# PCB_CHECKV3_2-20201218.net
KiCad netlist of a schematic drawn in Altium Designer
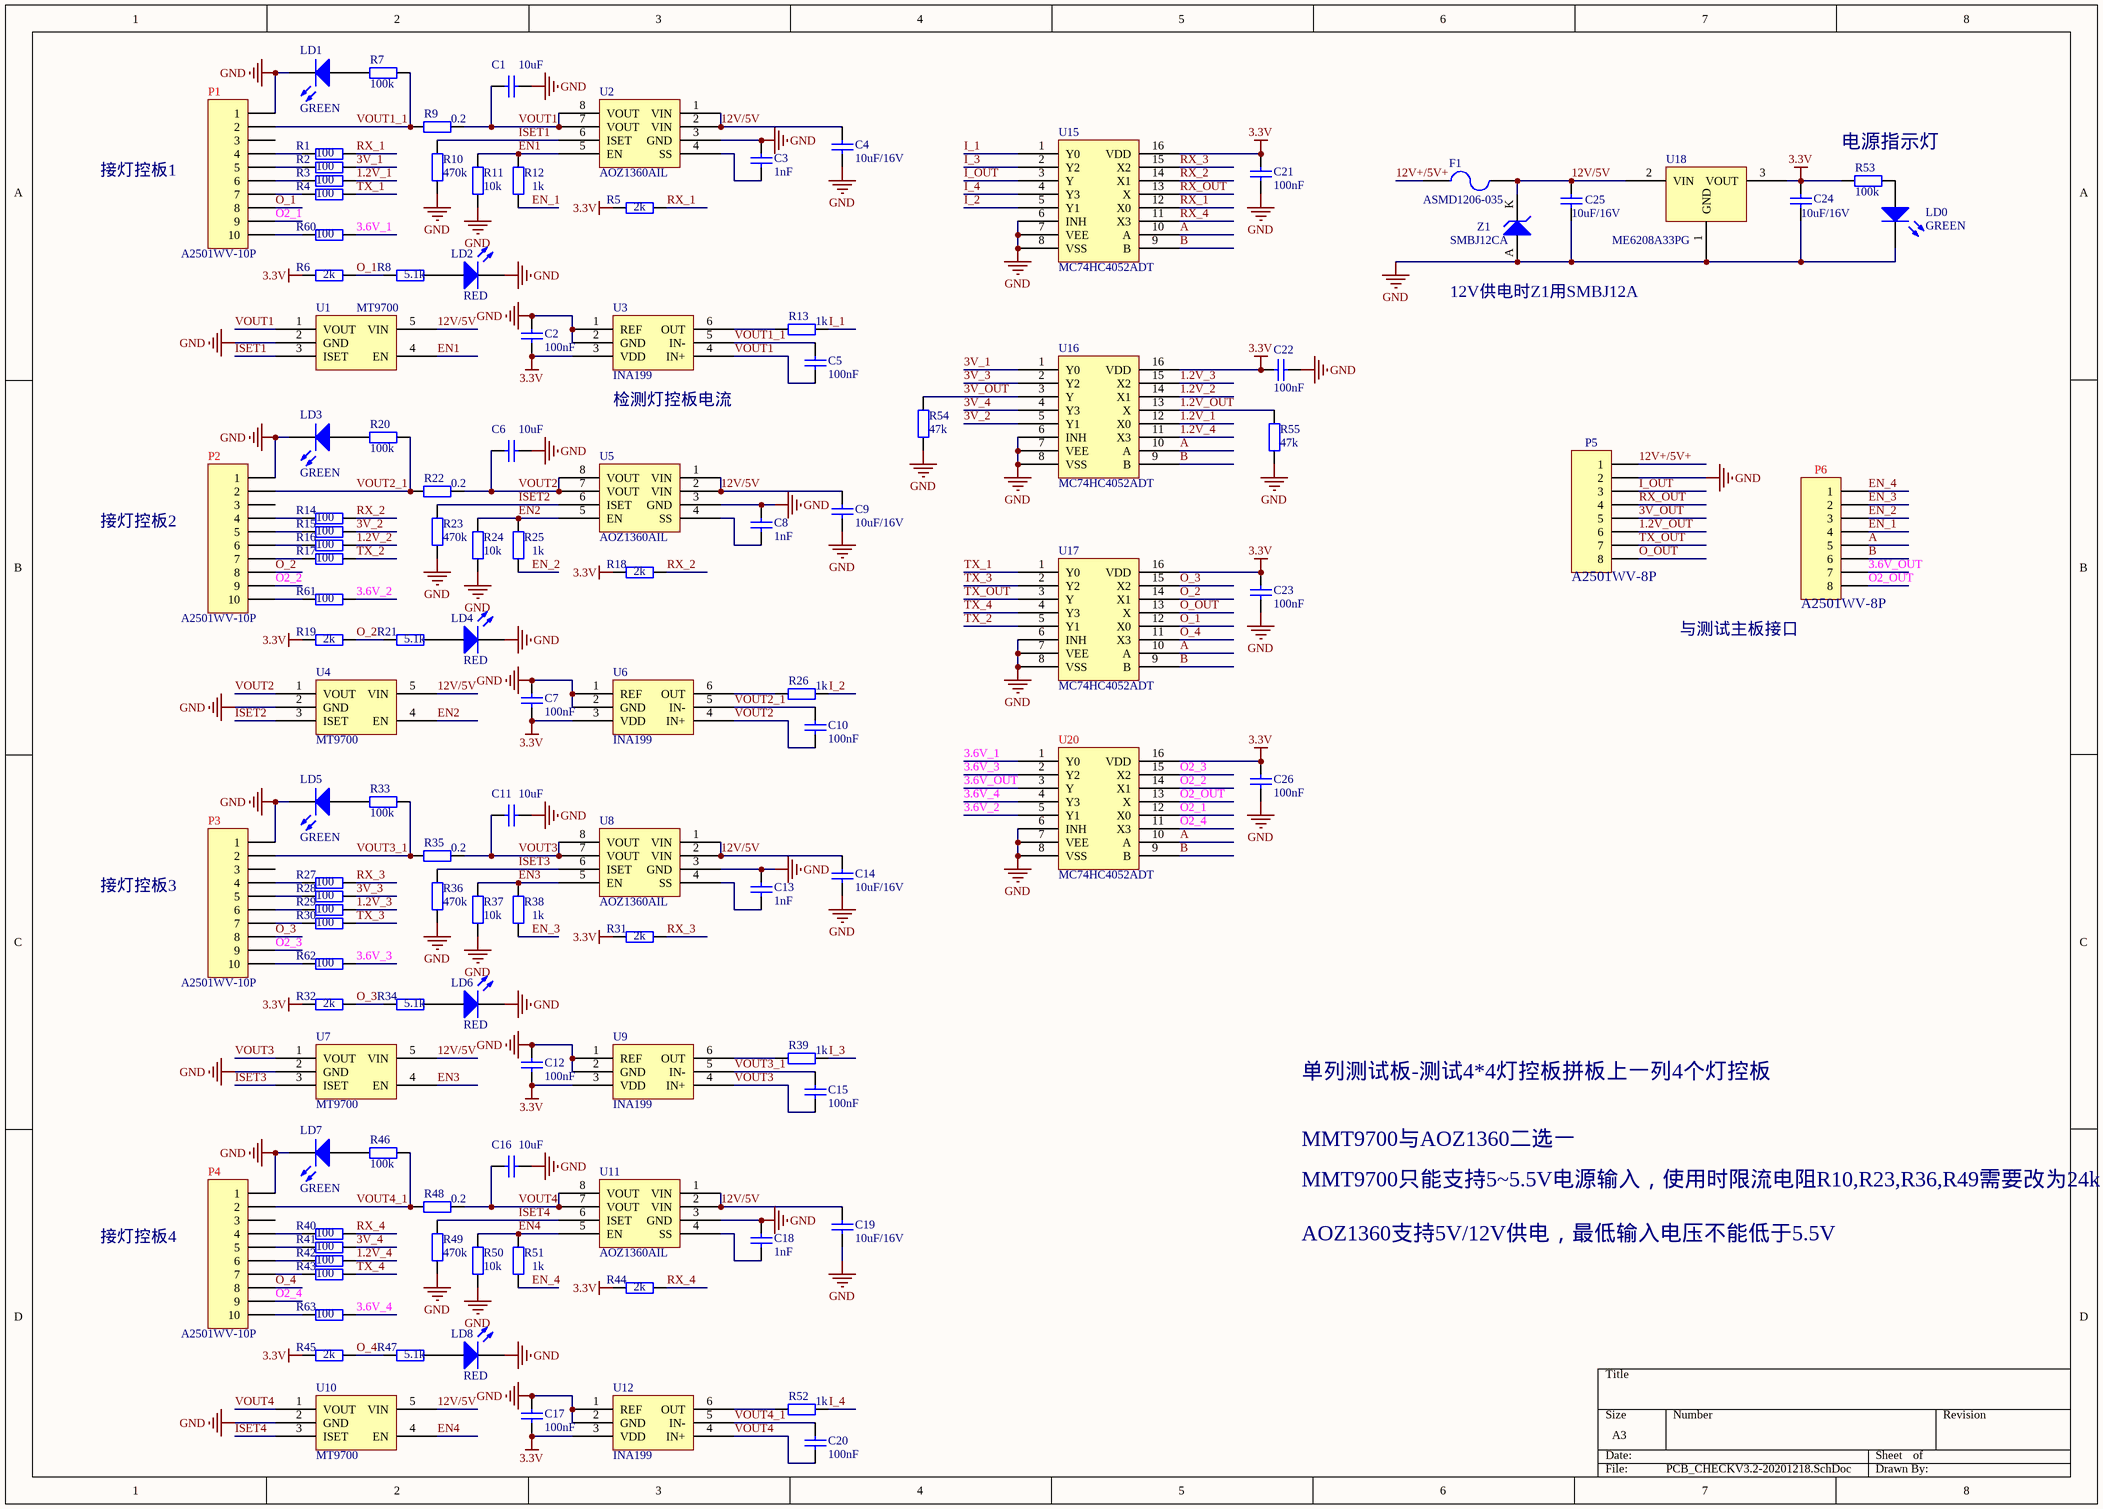
[diagram p0: PCB_CHECKV3.2-20201218.SchDoc]

(export (version "E")
  (design (tool "Eeschema 10.0.6"))
  (components
    (comp (ref "C1")
      (value "10uF")
      (footprint "C0603")
      (description "Capacitor")
      (libsource (lib "Miscellaneous Devices") (part "Cap"))
    )
    (comp (ref "C2")
      (value "100nF")
      (footprint "C0603")
      (description "Capacitor")
      (libsource (lib "Miscellaneous Devices") (part "Cap"))
    )
    (comp (ref "C3")
      (value "1nF")
      (footprint "C0603")
      (description "Capacitor")
      (libsource (lib "Miscellaneous Devices") (part "Cap"))
    )
    (comp (ref "C4")
      (value "10uF/16V")
      (footprint "C0603")
      (description "Capacitor")
      (libsource (lib "Miscellaneous Devices") (part "Cap"))
    )
    (comp (ref "C5")
      (value "100nF")
      (footprint "C0603")
      (description "Capacitor")
      (libsource (lib "Miscellaneous Devices") (part "Cap"))
    )
    (comp (ref "C6")
      (value "10uF")
      (footprint "C0603")
      (description "Capacitor")
      (libsource (lib "Miscellaneous Devices") (part "Cap"))
    )
    (comp (ref "C7")
      (value "100nF")
      (footprint "C0603")
      (description "Capacitor")
      (libsource (lib "Miscellaneous Devices") (part "Cap"))
    )
    (comp (ref "C8")
      (value "1nF")
      (footprint "C0603")
      (description "Capacitor")
      (libsource (lib "Miscellaneous Devices") (part "Cap"))
    )
    (comp (ref "C9")
      (value "10uF/16V")
      (footprint "C0603")
      (description "Capacitor")
      (libsource (lib "Miscellaneous Devices") (part "Cap"))
    )
    (comp (ref "C10")
      (value "100nF")
      (footprint "C0603")
      (description "Capacitor")
      (libsource (lib "Miscellaneous Devices") (part "Cap"))
    )
    (comp (ref "C11")
      (value "10uF")
      (footprint "C0603")
      (description "Capacitor")
      (libsource (lib "Miscellaneous Devices") (part "Cap"))
    )
    (comp (ref "C12")
      (value "100nF")
      (footprint "C0603")
      (description "Capacitor")
      (libsource (lib "Miscellaneous Devices") (part "Cap"))
    )
    (comp (ref "C13")
      (value "1nF")
      (footprint "C0603")
      (description "Capacitor")
      (libsource (lib "Miscellaneous Devices") (part "Cap"))
    )
    (comp (ref "C14")
      (value "10uF/16V")
      (footprint "C0603")
      (description "Capacitor")
      (libsource (lib "Miscellaneous Devices") (part "Cap"))
    )
    (comp (ref "C15")
      (value "100nF")
      (footprint "C0603")
      (description "Capacitor")
      (libsource (lib "Miscellaneous Devices") (part "Cap"))
    )
    (comp (ref "C16")
      (value "10uF")
      (footprint "C0603")
      (description "Capacitor")
      (libsource (lib "Miscellaneous Devices") (part "Cap"))
    )
    (comp (ref "C17")
      (value "100nF")
      (footprint "C0603")
      (description "Capacitor")
      (libsource (lib "Miscellaneous Devices") (part "Cap"))
    )
    (comp (ref "C18")
      (value "1nF")
      (footprint "C0603")
      (description "Capacitor")
      (libsource (lib "Miscellaneous Devices") (part "Cap"))
    )
    (comp (ref "C19")
      (value "10uF/16V")
      (footprint "C0603")
      (description "Capacitor")
      (libsource (lib "Miscellaneous Devices") (part "Cap"))
    )
    (comp (ref "C20")
      (value "100nF")
      (footprint "C0603")
      (description "Capacitor")
      (libsource (lib "Miscellaneous Devices") (part "Cap"))
    )
    (comp (ref "C21")
      (value "100nF")
      (footprint "C0603")
      (description "Capacitor")
      (libsource (lib "Miscellaneous Devices") (part "Cap"))
    )
    (comp (ref "C22")
      (value "100nF")
      (footprint "C0603")
      (description "Capacitor")
      (libsource (lib "Miscellaneous Devices") (part "Cap"))
    )
    (comp (ref "C23")
      (value "100nF")
      (footprint "C0603")
      (description "Capacitor")
      (libsource (lib "Miscellaneous Devices") (part "Cap"))
    )
    (comp (ref "C24")
      (value "10uF/16V")
      (footprint "C0603")
      (description "Capacitor")
      (libsource (lib "Miscellaneous Devices") (part "Cap"))
    )
    (comp (ref "C25")
      (value "10uF/16V")
      (footprint "C0603")
      (description "Capacitor")
      (libsource (lib "Miscellaneous Devices") (part "Cap"))
    )
    (comp (ref "C26")
      (value "100nF")
      (footprint "C0603")
      (description "Capacitor")
      (libsource (lib "Miscellaneous Devices") (part "Cap"))
    )
    (comp (ref "F1")
      (value "ASMD1206-035")
      (footprint "R1206")
      (description "Fuse")
      (libsource (lib "Miscellaneous Devices") (part "Fuse 2"))
    )
    (comp (ref "LD0")
      (value "GREEN")
      (footprint "LED-0603")
      (description "LED灯")
      (libsource (lib "*") (part "LED0"))
    )
    (comp (ref "LD1")
      (value "GREEN")
      (footprint "LED-0603")
      (description "LED灯")
      (libsource (lib "*") (part "LED0"))
    )
    (comp (ref "LD2")
      (value "RED")
      (footprint "LED-0603")
      (description "LED灯")
      (libsource (lib "*") (part "LED0"))
    )
    (comp (ref "LD3")
      (value "GREEN")
      (footprint "LED-0603")
      (description "LED灯")
      (libsource (lib "*") (part "LED0"))
    )
    (comp (ref "LD4")
      (value "RED")
      (footprint "LED-0603")
      (description "LED灯")
      (libsource (lib "*") (part "LED0"))
    )
    (comp (ref "LD5")
      (value "GREEN")
      (footprint "LED-0603")
      (description "LED灯")
      (libsource (lib "*") (part "LED0"))
    )
    (comp (ref "LD6")
      (value "RED")
      (footprint "LED-0603")
      (description "LED灯")
      (libsource (lib "*") (part "LED0"))
    )
    (comp (ref "LD7")
      (value "GREEN")
      (footprint "LED-0603")
      (description "LED灯")
      (libsource (lib "*") (part "LED0"))
    )
    (comp (ref "LD8")
      (value "RED")
      (footprint "LED-0603")
      (description "LED灯")
      (libsource (lib "*") (part "LED0"))
    )
    (comp (ref "P1")
      (value "A2501WV-10P")
      (footprint "XH2.5-8P")
      (description "Header, 8-Pin")
      (libsource (lib "PCB_CHECKV3.2-20201218") (part "Header 10"))
    )
    (comp (ref "P2")
      (value "A2501WV-10P")
      (footprint "XH2.5-8P")
      (description "Header, 8-Pin")
      (libsource (lib "PCB_CHECKV3.2-20201218") (part "Header 10"))
    )
    (comp (ref "P3")
      (value "A2501WV-10P")
      (footprint "XH2.5-8P")
      (description "Header, 8-Pin")
      (libsource (lib "PCB_CHECKV3.2-20201218") (part "Header 10"))
    )
    (comp (ref "P4")
      (value "A2501WV-10P")
      (footprint "XH2.5-8P")
      (description "Header, 8-Pin")
      (libsource (lib "PCB_CHECKV3.2-20201218") (part "Header 10"))
    )
    (comp (ref "P5")
      (value "A2501WV-8P")
      (footprint "XH2.5-8P")
      (description "Header, 8-Pin")
      (libsource (lib "Miscellaneous Connectors") (part "Header 8"))
    )
    (comp (ref "P6")
      (value "A2501WV-8P")
      (footprint "XH2.5-8P")
      (description "Header, 8-Pin")
      (libsource (lib "Miscellaneous Connectors") (part "Header 8"))
    )
    (comp (ref "R1")
      (value "100")
      (footprint "R0603")
      (description "Resistor")
      (libsource (lib "") (part "Res2_1"))
    )
    (comp (ref "R2")
      (value "100")
      (footprint "R0603")
      (description "Resistor")
      (libsource (lib "") (part "Res2_1"))
    )
    (comp (ref "R3")
      (value "100")
      (footprint "R0603")
      (description "Resistor")
      (libsource (lib "") (part "Res2_1"))
    )
    (comp (ref "R4")
      (value "100")
      (footprint "R0603")
      (description "Resistor")
      (libsource (lib "") (part "Res2_1"))
    )
    (comp (ref "R5")
      (value "2k")
      (footprint "R0603")
      (description "Resistor")
      (libsource (lib "") (part "Res2_1"))
    )
    (comp (ref "R6")
      (value "2k")
      (footprint "R0603")
      (description "Resistor")
      (libsource (lib "") (part "Res2_1"))
    )
    (comp (ref "R7")
      (value "100k")
      (footprint "R0603")
      (description "Resistor")
      (libsource (lib "") (part "Res2_2"))
    )
    (comp (ref "R8")
      (value "5.1k")
      (footprint "R0603")
      (description "Resistor")
      (libsource (lib "") (part "Res2_1"))
    )
    (comp (ref "R9")
      (value "0.2")
      (footprint "R0603")
      (description "Resistor")
      (libsource (lib "") (part "Res2_1"))
    )
    (comp (ref "R10")
      (value "470k")
      (footprint "R0603")
      (description "Resistor")
      (libsource (lib "Miscellaneous Devices") (part "Res2"))
    )
    (comp (ref "R11")
      (value "10k")
      (footprint "R0603")
      (description "Resistor")
      (libsource (lib "Miscellaneous Devices") (part "Res2"))
    )
    (comp (ref "R12")
      (value "1k")
      (footprint "R0603")
      (description "Resistor")
      (libsource (lib "Miscellaneous Devices") (part "Res2"))
    )
    (comp (ref "R13")
      (value "1k")
      (footprint "R0603")
      (description "Resistor")
      (libsource (lib "") (part "Res2_1"))
    )
    (comp (ref "R14")
      (value "100")
      (footprint "R0603")
      (description "Resistor")
      (libsource (lib "") (part "Res2_1"))
    )
    (comp (ref "R15")
      (value "100")
      (footprint "R0603")
      (description "Resistor")
      (libsource (lib "") (part "Res2_1"))
    )
    (comp (ref "R16")
      (value "100")
      (footprint "R0603")
      (description "Resistor")
      (libsource (lib "") (part "Res2_1"))
    )
    (comp (ref "R17")
      (value "100")
      (footprint "R0603")
      (description "Resistor")
      (libsource (lib "") (part "Res2_1"))
    )
    (comp (ref "R18")
      (value "2k")
      (footprint "R0603")
      (description "Resistor")
      (libsource (lib "") (part "Res2_1"))
    )
    (comp (ref "R19")
      (value "2k")
      (footprint "R0603")
      (description "Resistor")
      (libsource (lib "") (part "Res2_1"))
    )
    (comp (ref "R20")
      (value "100k")
      (footprint "R0603")
      (description "Resistor")
      (libsource (lib "") (part "Res2_2"))
    )
    (comp (ref "R21")
      (value "5.1k")
      (footprint "R0603")
      (description "Resistor")
      (libsource (lib "") (part "Res2_1"))
    )
    (comp (ref "R22")
      (value "0.2")
      (footprint "R0603")
      (description "Resistor")
      (libsource (lib "") (part "Res2_1"))
    )
    (comp (ref "R23")
      (value "470k")
      (footprint "R0603")
      (description "Resistor")
      (libsource (lib "Miscellaneous Devices") (part "Res2"))
    )
    (comp (ref "R24")
      (value "10k")
      (footprint "R0603")
      (description "Resistor")
      (libsource (lib "Miscellaneous Devices") (part "Res2"))
    )
    (comp (ref "R25")
      (value "1k")
      (footprint "R0603")
      (description "Resistor")
      (libsource (lib "Miscellaneous Devices") (part "Res2"))
    )
    (comp (ref "R26")
      (value "1k")
      (footprint "R0603")
      (description "Resistor")
      (libsource (lib "") (part "Res2_1"))
    )
    (comp (ref "R27")
      (value "100")
      (footprint "R0603")
      (description "Resistor")
      (libsource (lib "") (part "Res2_1"))
    )
    (comp (ref "R28")
      (value "100")
      (footprint "R0603")
      (description "Resistor")
      (libsource (lib "") (part "Res2_1"))
    )
    (comp (ref "R29")
      (value "100")
      (footprint "R0603")
      (description "Resistor")
      (libsource (lib "") (part "Res2_1"))
    )
    (comp (ref "R30")
      (value "100")
      (footprint "R0603")
      (description "Resistor")
      (libsource (lib "") (part "Res2_1"))
    )
    (comp (ref "R31")
      (value "2k")
      (footprint "R0603")
      (description "Resistor")
      (libsource (lib "") (part "Res2_1"))
    )
    (comp (ref "R32")
      (value "2k")
      (footprint "R0603")
      (description "Resistor")
      (libsource (lib "") (part "Res2_1"))
    )
    (comp (ref "R33")
      (value "100k")
      (footprint "R0603")
      (description "Resistor")
      (libsource (lib "") (part "Res2_2"))
    )
    (comp (ref "R34")
      (value "5.1k")
      (footprint "R0603")
      (description "Resistor")
      (libsource (lib "") (part "Res2_1"))
    )
    (comp (ref "R35")
      (value "0.2")
      (footprint "R0603")
      (description "Resistor")
      (libsource (lib "") (part "Res2_1"))
    )
    (comp (ref "R36")
      (value "470k")
      (footprint "R0603")
      (description "Resistor")
      (libsource (lib "Miscellaneous Devices") (part "Res2"))
    )
    (comp (ref "R37")
      (value "10k")
      (footprint "R0603")
      (description "Resistor")
      (libsource (lib "Miscellaneous Devices") (part "Res2"))
    )
    (comp (ref "R38")
      (value "1k")
      (footprint "R0603")
      (description "Resistor")
      (libsource (lib "Miscellaneous Devices") (part "Res2"))
    )
    (comp (ref "R39")
      (value "1k")
      (footprint "R0603")
      (description "Resistor")
      (libsource (lib "") (part "Res2_1"))
    )
    (comp (ref "R40")
      (value "100")
      (footprint "R0603")
      (description "Resistor")
      (libsource (lib "") (part "Res2_1"))
    )
    (comp (ref "R41")
      (value "100")
      (footprint "R0603")
      (description "Resistor")
      (libsource (lib "") (part "Res2_1"))
    )
    (comp (ref "R42")
      (value "100")
      (footprint "R0603")
      (description "Resistor")
      (libsource (lib "") (part "Res2_1"))
    )
    (comp (ref "R43")
      (value "100")
      (footprint "R0603")
      (description "Resistor")
      (libsource (lib "") (part "Res2_1"))
    )
    (comp (ref "R44")
      (value "2k")
      (footprint "R0603")
      (description "Resistor")
      (libsource (lib "") (part "Res2_1"))
    )
    (comp (ref "R45")
      (value "2k")
      (footprint "R0603")
      (description "Resistor")
      (libsource (lib "") (part "Res2_1"))
    )
    (comp (ref "R46")
      (value "100k")
      (footprint "R0603")
      (description "Resistor")
      (libsource (lib "") (part "Res2_2"))
    )
    (comp (ref "R47")
      (value "5.1k")
      (footprint "R0603")
      (description "Resistor")
      (libsource (lib "") (part "Res2_1"))
    )
    (comp (ref "R48")
      (value "0.2")
      (footprint "R0603")
      (description "Resistor")
      (libsource (lib "") (part "Res2_1"))
    )
    (comp (ref "R49")
      (value "470k")
      (footprint "R0603")
      (description "Resistor")
      (libsource (lib "Miscellaneous Devices") (part "Res2"))
    )
    (comp (ref "R50")
      (value "10k")
      (footprint "R0603")
      (description "Resistor")
      (libsource (lib "Miscellaneous Devices") (part "Res2"))
    )
    (comp (ref "R51")
      (value "1k")
      (footprint "R0603")
      (description "Resistor")
      (libsource (lib "Miscellaneous Devices") (part "Res2"))
    )
    (comp (ref "R52")
      (value "1k")
      (footprint "R0603")
      (description "Resistor")
      (libsource (lib "") (part "Res2_1"))
    )
    (comp (ref "R53")
      (value "100k")
      (footprint "R0603")
      (description "Resistor")
      (libsource (lib "") (part "Res2_1"))
    )
    (comp (ref "R54")
      (value "47k")
      (footprint "R0603")
      (description "Resistor")
      (libsource (lib "Miscellaneous Devices") (part "Res2"))
    )
    (comp (ref "R55")
      (value "47k")
      (footprint "R0603")
      (description "Resistor")
      (libsource (lib "Miscellaneous Devices") (part "Res2"))
    )
    (comp (ref "R60")
      (value "100")
      (footprint "R0603")
      (description "Resistor")
      (libsource (lib "") (part "Res2_1"))
    )
    (comp (ref "R61")
      (value "100")
      (footprint "R0603")
      (description "Resistor")
      (libsource (lib "") (part "Res2_1"))
    )
    (comp (ref "R62")
      (value "100")
      (footprint "R0603")
      (description "Resistor")
      (libsource (lib "") (part "Res2_1"))
    )
    (comp (ref "R63")
      (value "100")
      (footprint "R0603")
      (description "Resistor")
      (libsource (lib "") (part "Res2_1"))
    )
    (comp (ref "U1") (value "MT9700") (footprint "SOT23-5") (libsource (lib "Schlib1") (part "MT9700")))
    (comp (ref "U2")
      (value "AOZ1360AIL")
      (footprint "My Footprint View:SO-8S")
      (libsource (lib "Schlib1") (part "AOZ1360AIL"))
    )
    (comp (ref "U3") (value "INA199") (footprint "SC70-6") (libsource (lib "Schlib1") (part "INA199")))
    (comp (ref "U4") (value "MT9700") (footprint "SOT23-5") (libsource (lib "Schlib1") (part "MT9700")))
    (comp (ref "U5")
      (value "AOZ1360AIL")
      (footprint "My Footprint View:SO-8S")
      (libsource (lib "Schlib1") (part "AOZ1360AIL"))
    )
    (comp (ref "U6") (value "INA199") (footprint "SC70-6") (libsource (lib "Schlib1") (part "INA199")))
    (comp (ref "U7") (value "MT9700") (footprint "SOT23-5") (libsource (lib "Schlib1") (part "MT9700")))
    (comp (ref "U8")
      (value "AOZ1360AIL")
      (footprint "My Footprint View:SO-8S")
      (libsource (lib "Schlib1") (part "AOZ1360AIL"))
    )
    (comp (ref "U9") (value "INA199") (footprint "SC70-6") (libsource (lib "Schlib1") (part "INA199")))
    (comp (ref "U10") (value "MT9700") (footprint "SOT23-5") (libsource (lib "Schlib1") (part "MT9700")))
    (comp (ref "U11")
      (value "AOZ1360AIL")
      (footprint "My Footprint View:SO-8S")
      (libsource (lib "Schlib1") (part "AOZ1360AIL"))
    )
    (comp (ref "U12") (value "INA199") (footprint "SC70-6") (libsource (lib "Schlib1") (part "INA199")))
    (comp (ref "U15")
      (value "MC74HC4052ADT")
      (footprint "PCBLIB:TSSOP16_N")
      (libsource (lib "Schlib1") (part "CD4052"))
    )
    (comp (ref "U16")
      (value "MC74HC4052ADT")
      (footprint "TSSOP16_N")
      (libsource (lib "Schlib1") (part "CD4052"))
    )
    (comp (ref "U17")
      (value "MC74HC4052ADT")
      (footprint "TSSOP16_N")
      (libsource (lib "Schlib1") (part "CD4052"))
    )
    (comp (ref "U18")
      (value "ME6208A33PG")
      (footprint "My Footprint View:SOT89N")
      (libsource (lib "Schlib1") (part "ME6208A50PG"))
    )
    (comp (ref "U20")
      (value "MC74HC4052ADT")
      (footprint "TSSOP16_N")
      (libsource (lib "Schlib1") (part "CD4052"))
    )
    (comp (ref "Z1")
      (value "SMBJ12CA")
      (footprint "PCBLIB:SMB")
      (description "Zener Diode")
      (libsource (lib "Miscellaneous Devices") (part "D Zener"))
    )
  )
  (nets
    (net (code "1") (name "/1.2V_1") (class "Default")
      (node (ref "R3") (pin "2") (pinfunction "2_2") (pintype "passive"))
      (node (ref "U16") (pin "12") (pinfunction "X0_12") (pintype "passive"))
    )
    (net (code "2") (name "/1.2V_2") (class "Default")
      (node (ref "R16") (pin "2") (pinfunction "2_2") (pintype "passive"))
      (node (ref "U16") (pin "14") (pinfunction "X1_14") (pintype "passive"))
    )
    (net (code "3") (name "/1.2V_3") (class "Default")
      (node (ref "R29") (pin "2") (pinfunction "2_2") (pintype "passive"))
      (node (ref "U16") (pin "15") (pinfunction "X2_15") (pintype "passive"))
    )
    (net (code "4") (name "/1.2V_4") (class "Default")
      (node (ref "R42") (pin "2") (pinfunction "2_2") (pintype "passive"))
      (node (ref "U16") (pin "11") (pinfunction "X3_11") (pintype "passive"))
    )
    (net (code "5") (name "/1.2V_OUT") (class "Default")
      (node (ref "P5") (pin "6") (pinfunction "6_6") (pintype "passive"))
      (node (ref "R55") (pin "1") (pinfunction "1_1") (pintype "passive"))
      (node (ref "U16") (pin "13") (pinfunction "X_13") (pintype "passive"))
    )
    (net (code "6") (name "/3.6V_1") (class "Default")
      (node (ref "R60") (pin "2") (pinfunction "2_2") (pintype "passive"))
      (node (ref "U20") (pin "1") (pinfunction "Y0_1") (pintype "passive"))
    )
    (net (code "7") (name "/3.6V_2") (class "Default")
      (node (ref "R61") (pin "2") (pinfunction "2_2") (pintype "passive"))
      (node (ref "U20") (pin "5") (pinfunction "Y1_5") (pintype "passive"))
    )
    (net (code "8") (name "/3.6V_3") (class "Default")
      (node (ref "R62") (pin "2") (pinfunction "2_2") (pintype "passive"))
      (node (ref "U20") (pin "2") (pinfunction "Y2_2") (pintype "passive"))
    )
    (net (code "9") (name "/3.6V_4") (class "Default")
      (node (ref "R63") (pin "2") (pinfunction "2_2") (pintype "passive"))
      (node (ref "U20") (pin "4") (pinfunction "Y3_4") (pintype "passive"))
    )
    (net (code "10") (name "/3.6V_OUT") (class "Default")
      (node (ref "P6") (pin "7") (pinfunction "7_7") (pintype "passive"))
      (node (ref "U20") (pin "3") (pinfunction "Y_3") (pintype "passive"))
    )
    (net (code "11") (name "/3V_1") (class "Default")
      (node (ref "R2") (pin "2") (pinfunction "2_2") (pintype "passive"))
      (node (ref "U16") (pin "1") (pinfunction "Y0_1") (pintype "passive"))
    )
    (net (code "12") (name "/3V_2") (class "Default")
      (node (ref "R15") (pin "2") (pinfunction "2_2") (pintype "passive"))
      (node (ref "U16") (pin "5") (pinfunction "Y1_5") (pintype "passive"))
    )
    (net (code "13") (name "/3V_3") (class "Default")
      (node (ref "R28") (pin "2") (pinfunction "2_2") (pintype "passive"))
      (node (ref "U16") (pin "2") (pinfunction "Y2_2") (pintype "passive"))
    )
    (net (code "14") (name "/3V_4") (class "Default")
      (node (ref "R41") (pin "2") (pinfunction "2_2") (pintype "passive"))
      (node (ref "U16") (pin "4") (pinfunction "Y3_4") (pintype "passive"))
    )
    (net (code "15") (name "/3V_OUT") (class "Default")
      (node (ref "P5") (pin "5") (pinfunction "5_5") (pintype "passive"))
      (node (ref "R54") (pin "1") (pinfunction "1_1") (pintype "passive"))
      (node (ref "U16") (pin "3") (pinfunction "Y_3") (pintype "passive"))
    )
    (net (code "16") (name "/12V+{slash}5V+") (class "Default")
      (node (ref "F1") (pin "1") (pinfunction "1_1") (pintype "passive"))
      (node (ref "P5") (pin "1") (pinfunction "1_1") (pintype "passive"))
    )
    (net (code "17") (name "/12V{slash}5V") (class "Default")
      (node (ref "C14") (pin "1") (pinfunction "1_1") (pintype "passive"))
      (node (ref "C19") (pin "1") (pinfunction "1_1") (pintype "passive"))
      (node (ref "C25") (pin "1") (pinfunction "1_1") (pintype "passive"))
      (node (ref "C4") (pin "1") (pinfunction "1_1") (pintype "passive"))
      (node (ref "C9") (pin "1") (pinfunction "1_1") (pintype "passive"))
      (node (ref "F1") (pin "2") (pinfunction "2_2") (pintype "passive"))
      (node (ref "U1") (pin "5") (pinfunction "VIN_5") (pintype "passive"))
      (node (ref "U10") (pin "5") (pinfunction "VIN_5") (pintype "passive"))
      (node (ref "U11") (pin "1") (pinfunction "VIN_1") (pintype "passive"))
      (node (ref "U11") (pin "2") (pinfunction "VIN_2") (pintype "passive"))
      (node (ref "U18") (pin "2") (pinfunction "VIN_2") (pintype "passive"))
      (node (ref "U2") (pin "1") (pinfunction "VIN_1") (pintype "passive"))
      (node (ref "U2") (pin "2") (pinfunction "VIN_2") (pintype "passive"))
      (node (ref "U4") (pin "5") (pinfunction "VIN_5") (pintype "passive"))
      (node (ref "U5") (pin "1") (pinfunction "VIN_1") (pintype "passive"))
      (node (ref "U5") (pin "2") (pinfunction "VIN_2") (pintype "passive"))
      (node (ref "U7") (pin "5") (pinfunction "VIN_5") (pintype "passive"))
      (node (ref "U8") (pin "1") (pinfunction "VIN_1") (pintype "passive"))
      (node (ref "U8") (pin "2") (pinfunction "VIN_2") (pintype "passive"))
      (node (ref "Z1") (pin "K") (pinfunction "K_K") (pintype "passive"))
    )
    (net (code "18") (name "/A") (class "Default")
      (node (ref "P6") (pin "5") (pinfunction "5_5") (pintype "passive"))
      (node (ref "U15") (pin "10") (pinfunction "A_10") (pintype "passive"))
      (node (ref "U16") (pin "10") (pinfunction "A_10") (pintype "passive"))
      (node (ref "U17") (pin "10") (pinfunction "A_10") (pintype "passive"))
      (node (ref "U20") (pin "10") (pinfunction "A_10") (pintype "passive"))
    )
    (net (code "19") (name "/B") (class "Default")
      (node (ref "P6") (pin "6") (pinfunction "6_6") (pintype "passive"))
      (node (ref "U15") (pin "9") (pinfunction "B_9") (pintype "passive"))
      (node (ref "U16") (pin "9") (pinfunction "B_9") (pintype "passive"))
      (node (ref "U17") (pin "9") (pinfunction "B_9") (pintype "passive"))
      (node (ref "U20") (pin "9") (pinfunction "B_9") (pintype "passive"))
    )
    (net (code "20") (name "/EN1") (class "Default")
      (node (ref "R11") (pin "1") (pinfunction "1_1") (pintype "passive"))
      (node (ref "R12") (pin "1") (pinfunction "1_1") (pintype "passive"))
      (node (ref "U1") (pin "4") (pinfunction "EN_4") (pintype "passive"))
      (node (ref "U2") (pin "5") (pinfunction "EN_5") (pintype "passive"))
    )
    (net (code "21") (name "/EN2") (class "Default")
      (node (ref "R24") (pin "1") (pinfunction "1_1") (pintype "passive"))
      (node (ref "R25") (pin "1") (pinfunction "1_1") (pintype "passive"))
      (node (ref "U4") (pin "4") (pinfunction "EN_4") (pintype "passive"))
      (node (ref "U5") (pin "5") (pinfunction "EN_5") (pintype "passive"))
    )
    (net (code "22") (name "/EN3") (class "Default")
      (node (ref "R37") (pin "1") (pinfunction "1_1") (pintype "passive"))
      (node (ref "R38") (pin "1") (pinfunction "1_1") (pintype "passive"))
      (node (ref "U7") (pin "4") (pinfunction "EN_4") (pintype "passive"))
      (node (ref "U8") (pin "5") (pinfunction "EN_5") (pintype "passive"))
    )
    (net (code "23") (name "/EN4") (class "Default")
      (node (ref "R50") (pin "1") (pinfunction "1_1") (pintype "passive"))
      (node (ref "R51") (pin "1") (pinfunction "1_1") (pintype "passive"))
      (node (ref "U10") (pin "4") (pinfunction "EN_4") (pintype "passive"))
      (node (ref "U11") (pin "5") (pinfunction "EN_5") (pintype "passive"))
    )
    (net (code "24") (name "/EN_1") (class "Default")
      (node (ref "P6") (pin "4") (pinfunction "4_4") (pintype "passive"))
      (node (ref "R12") (pin "2") (pinfunction "2_2") (pintype "passive"))
    )
    (net (code "25") (name "/EN_2") (class "Default")
      (node (ref "P6") (pin "3") (pinfunction "3_3") (pintype "passive"))
      (node (ref "R25") (pin "2") (pinfunction "2_2") (pintype "passive"))
    )
    (net (code "26") (name "/EN_3") (class "Default")
      (node (ref "P6") (pin "2") (pinfunction "2_2") (pintype "passive"))
      (node (ref "R38") (pin "2") (pinfunction "2_2") (pintype "passive"))
    )
    (net (code "27") (name "/EN_4") (class "Default")
      (node (ref "P6") (pin "1") (pinfunction "1_1") (pintype "passive"))
      (node (ref "R51") (pin "2") (pinfunction "2_2") (pintype "passive"))
    )
    (net (code "28") (name "/ISET1") (class "Default")
      (node (ref "R10") (pin "1") (pinfunction "1_1") (pintype "passive"))
      (node (ref "U1") (pin "3") (pinfunction "ISET_3") (pintype "passive"))
      (node (ref "U2") (pin "6") (pinfunction "ISET_6") (pintype "passive"))
    )
    (net (code "29") (name "/ISET2") (class "Default")
      (node (ref "R23") (pin "1") (pinfunction "1_1") (pintype "passive"))
      (node (ref "U4") (pin "3") (pinfunction "ISET_3") (pintype "passive"))
      (node (ref "U5") (pin "6") (pinfunction "ISET_6") (pintype "passive"))
    )
    (net (code "30") (name "/ISET3") (class "Default")
      (node (ref "R36") (pin "1") (pinfunction "1_1") (pintype "passive"))
      (node (ref "U7") (pin "3") (pinfunction "ISET_3") (pintype "passive"))
      (node (ref "U8") (pin "6") (pinfunction "ISET_6") (pintype "passive"))
    )
    (net (code "31") (name "/ISET4") (class "Default")
      (node (ref "R49") (pin "1") (pinfunction "1_1") (pintype "passive"))
      (node (ref "U10") (pin "3") (pinfunction "ISET_3") (pintype "passive"))
      (node (ref "U11") (pin "6") (pinfunction "ISET_6") (pintype "passive"))
    )
    (net (code "32") (name "/I_1") (class "Default")
      (node (ref "R13") (pin "2") (pinfunction "2_2") (pintype "passive"))
      (node (ref "U15") (pin "1") (pinfunction "Y0_1") (pintype "passive"))
    )
    (net (code "33") (name "/I_2") (class "Default")
      (node (ref "R26") (pin "2") (pinfunction "2_2") (pintype "passive"))
      (node (ref "U15") (pin "5") (pinfunction "Y1_5") (pintype "passive"))
    )
    (net (code "34") (name "/I_3") (class "Default")
      (node (ref "R39") (pin "2") (pinfunction "2_2") (pintype "passive"))
      (node (ref "U15") (pin "2") (pinfunction "Y2_2") (pintype "passive"))
    )
    (net (code "35") (name "/I_4") (class "Default")
      (node (ref "R52") (pin "2") (pinfunction "2_2") (pintype "passive"))
      (node (ref "U15") (pin "4") (pinfunction "Y3_4") (pintype "passive"))
    )
    (net (code "36") (name "/I_OUT") (class "Default")
      (node (ref "P5") (pin "3") (pinfunction "3_3") (pintype "passive"))
      (node (ref "U15") (pin "3") (pinfunction "Y_3") (pintype "passive"))
    )
    (net (code "37") (name "/O2_1") (class "Default")
      (node (ref "P1") (pin "9") (pinfunction "9_9") (pintype "passive"))
      (node (ref "U20") (pin "12") (pinfunction "X0_12") (pintype "passive"))
    )
    (net (code "38") (name "/O2_2") (class "Default")
      (node (ref "P2") (pin "9") (pinfunction "9_9") (pintype "passive"))
      (node (ref "U20") (pin "14") (pinfunction "X1_14") (pintype "passive"))
    )
    (net (code "39") (name "/O2_3") (class "Default")
      (node (ref "P3") (pin "9") (pinfunction "9_9") (pintype "passive"))
      (node (ref "U20") (pin "15") (pinfunction "X2_15") (pintype "passive"))
    )
    (net (code "40") (name "/O2_4") (class "Default")
      (node (ref "P4") (pin "9") (pinfunction "9_9") (pintype "passive"))
      (node (ref "U20") (pin "11") (pinfunction "X3_11") (pintype "passive"))
    )
    (net (code "41") (name "/O2_OUT") (class "Default")
      (node (ref "P6") (pin "8") (pinfunction "8_8") (pintype "passive"))
      (node (ref "U20") (pin "13") (pinfunction "X_13") (pintype "passive"))
    )
    (net (code "42") (name "/O_1") (class "Default")
      (node (ref "P1") (pin "8") (pinfunction "8_8") (pintype "passive"))
      (node (ref "R6") (pin "2") (pinfunction "2_2") (pintype "passive"))
      (node (ref "R8") (pin "1") (pinfunction "1_1") (pintype "passive"))
      (node (ref "U17") (pin "12") (pinfunction "X0_12") (pintype "passive"))
    )
    (net (code "43") (name "/O_2") (class "Default")
      (node (ref "P2") (pin "8") (pinfunction "8_8") (pintype "passive"))
      (node (ref "R19") (pin "2") (pinfunction "2_2") (pintype "passive"))
      (node (ref "R21") (pin "1") (pinfunction "1_1") (pintype "passive"))
      (node (ref "U17") (pin "14") (pinfunction "X1_14") (pintype "passive"))
    )
    (net (code "44") (name "/O_3") (class "Default")
      (node (ref "P3") (pin "8") (pinfunction "8_8") (pintype "passive"))
      (node (ref "R32") (pin "2") (pinfunction "2_2") (pintype "passive"))
      (node (ref "R34") (pin "1") (pinfunction "1_1") (pintype "passive"))
      (node (ref "U17") (pin "15") (pinfunction "X2_15") (pintype "passive"))
    )
    (net (code "45") (name "/O_4") (class "Default")
      (node (ref "P4") (pin "8") (pinfunction "8_8") (pintype "passive"))
      (node (ref "R45") (pin "2") (pinfunction "2_2") (pintype "passive"))
      (node (ref "R47") (pin "1") (pinfunction "1_1") (pintype "passive"))
      (node (ref "U17") (pin "11") (pinfunction "X3_11") (pintype "passive"))
    )
    (net (code "46") (name "/O_OUT") (class "Default")
      (node (ref "P5") (pin "8") (pinfunction "8_8") (pintype "passive"))
      (node (ref "U17") (pin "13") (pinfunction "X_13") (pintype "passive"))
    )
    (net (code "47") (name "/RX_1") (class "Default")
      (node (ref "R1") (pin "2") (pinfunction "2_2") (pintype "passive"))
      (node (ref "R5") (pin "2") (pinfunction "2_2") (pintype "passive"))
      (node (ref "U15") (pin "12") (pinfunction "X0_12") (pintype "passive"))
    )
    (net (code "48") (name "/RX_2") (class "Default")
      (node (ref "R14") (pin "2") (pinfunction "2_2") (pintype "passive"))
      (node (ref "R18") (pin "2") (pinfunction "2_2") (pintype "passive"))
      (node (ref "U15") (pin "14") (pinfunction "X1_14") (pintype "passive"))
    )
    (net (code "49") (name "/RX_3") (class "Default")
      (node (ref "R27") (pin "2") (pinfunction "2_2") (pintype "passive"))
      (node (ref "R31") (pin "2") (pinfunction "2_2") (pintype "passive"))
      (node (ref "U15") (pin "15") (pinfunction "X2_15") (pintype "passive"))
    )
    (net (code "50") (name "/RX_4") (class "Default")
      (node (ref "R40") (pin "2") (pinfunction "2_2") (pintype "passive"))
      (node (ref "R44") (pin "2") (pinfunction "2_2") (pintype "passive"))
      (node (ref "U15") (pin "11") (pinfunction "X3_11") (pintype "passive"))
    )
    (net (code "51") (name "/RX_OUT") (class "Default")
      (node (ref "P5") (pin "4") (pinfunction "4_4") (pintype "passive"))
      (node (ref "U15") (pin "13") (pinfunction "X_13") (pintype "passive"))
    )
    (net (code "52") (name "/TX_1") (class "Default")
      (node (ref "R4") (pin "2") (pinfunction "2_2") (pintype "passive"))
      (node (ref "U17") (pin "1") (pinfunction "Y0_1") (pintype "passive"))
    )
    (net (code "53") (name "/TX_2") (class "Default")
      (node (ref "R17") (pin "2") (pinfunction "2_2") (pintype "passive"))
      (node (ref "U17") (pin "5") (pinfunction "Y1_5") (pintype "passive"))
    )
    (net (code "54") (name "/TX_3") (class "Default")
      (node (ref "R30") (pin "2") (pinfunction "2_2") (pintype "passive"))
      (node (ref "U17") (pin "2") (pinfunction "Y2_2") (pintype "passive"))
    )
    (net (code "55") (name "/TX_4") (class "Default")
      (node (ref "R43") (pin "2") (pinfunction "2_2") (pintype "passive"))
      (node (ref "U17") (pin "4") (pinfunction "Y3_4") (pintype "passive"))
    )
    (net (code "56") (name "/TX_OUT") (class "Default")
      (node (ref "P5") (pin "7") (pinfunction "7_7") (pintype "passive"))
      (node (ref "U17") (pin "3") (pinfunction "Y_3") (pintype "passive"))
    )
    (net (code "57") (name "/VOUT1") (class "Default")
      (node (ref "C1") (pin "1") (pinfunction "1_1") (pintype "passive"))
      (node (ref "C5") (pin "1") (pinfunction "1_1") (pintype "passive"))
      (node (ref "R9") (pin "2") (pinfunction "2_2") (pintype "passive"))
      (node (ref "U1") (pin "1") (pinfunction "VOUT_1") (pintype "passive"))
      (node (ref "U2") (pin "7") (pinfunction "VOUT_7") (pintype "passive"))
      (node (ref "U2") (pin "8") (pinfunction "VOUT_8") (pintype "passive"))
      (node (ref "U3") (pin "4") (pinfunction "IN+_4") (pintype "passive"))
    )
    (net (code "58") (name "/VOUT1_1") (class "Default")
      (node (ref "C5") (pin "2") (pinfunction "2_2") (pintype "passive"))
      (node (ref "P1") (pin "2") (pinfunction "2_2") (pintype "passive"))
      (node (ref "R7") (pin "1") (pinfunction "1_1") (pintype "passive"))
      (node (ref "R9") (pin "1") (pinfunction "1_1") (pintype "passive"))
      (node (ref "U3") (pin "5") (pinfunction "IN-_5") (pintype "passive"))
    )
    (net (code "59") (name "/VOUT2") (class "Default")
      (node (ref "C10") (pin "1") (pinfunction "1_1") (pintype "passive"))
      (node (ref "C6") (pin "1") (pinfunction "1_1") (pintype "passive"))
      (node (ref "R22") (pin "2") (pinfunction "2_2") (pintype "passive"))
      (node (ref "U4") (pin "1") (pinfunction "VOUT_1") (pintype "passive"))
      (node (ref "U5") (pin "7") (pinfunction "VOUT_7") (pintype "passive"))
      (node (ref "U5") (pin "8") (pinfunction "VOUT_8") (pintype "passive"))
      (node (ref "U6") (pin "4") (pinfunction "IN+_4") (pintype "passive"))
    )
    (net (code "60") (name "/VOUT2_1") (class "Default")
      (node (ref "C10") (pin "2") (pinfunction "2_2") (pintype "passive"))
      (node (ref "P2") (pin "2") (pinfunction "2_2") (pintype "passive"))
      (node (ref "R20") (pin "1") (pinfunction "1_1") (pintype "passive"))
      (node (ref "R22") (pin "1") (pinfunction "1_1") (pintype "passive"))
      (node (ref "U6") (pin "5") (pinfunction "IN-_5") (pintype "passive"))
    )
    (net (code "61") (name "/VOUT3") (class "Default")
      (node (ref "C11") (pin "1") (pinfunction "1_1") (pintype "passive"))
      (node (ref "C15") (pin "1") (pinfunction "1_1") (pintype "passive"))
      (node (ref "R35") (pin "2") (pinfunction "2_2") (pintype "passive"))
      (node (ref "U7") (pin "1") (pinfunction "VOUT_1") (pintype "passive"))
      (node (ref "U8") (pin "7") (pinfunction "VOUT_7") (pintype "passive"))
      (node (ref "U8") (pin "8") (pinfunction "VOUT_8") (pintype "passive"))
      (node (ref "U9") (pin "4") (pinfunction "IN+_4") (pintype "passive"))
    )
    (net (code "62") (name "/VOUT3_1") (class "Default")
      (node (ref "C15") (pin "2") (pinfunction "2_2") (pintype "passive"))
      (node (ref "P3") (pin "2") (pinfunction "2_2") (pintype "passive"))
      (node (ref "R33") (pin "1") (pinfunction "1_1") (pintype "passive"))
      (node (ref "R35") (pin "1") (pinfunction "1_1") (pintype "passive"))
      (node (ref "U9") (pin "5") (pinfunction "IN-_5") (pintype "passive"))
    )
    (net (code "63") (name "/VOUT4") (class "Default")
      (node (ref "C16") (pin "1") (pinfunction "1_1") (pintype "passive"))
      (node (ref "C20") (pin "1") (pinfunction "1_1") (pintype "passive"))
      (node (ref "R48") (pin "2") (pinfunction "2_2") (pintype "passive"))
      (node (ref "U10") (pin "1") (pinfunction "VOUT_1") (pintype "passive"))
      (node (ref "U11") (pin "7") (pinfunction "VOUT_7") (pintype "passive"))
      (node (ref "U11") (pin "8") (pinfunction "VOUT_8") (pintype "passive"))
      (node (ref "U12") (pin "4") (pinfunction "IN+_4") (pintype "passive"))
    )
    (net (code "64") (name "/VOUT4_1") (class "Default")
      (node (ref "C20") (pin "2") (pinfunction "2_2") (pintype "passive"))
      (node (ref "P4") (pin "2") (pinfunction "2_2") (pintype "passive"))
      (node (ref "R46") (pin "1") (pinfunction "1_1") (pintype "passive"))
      (node (ref "R48") (pin "1") (pinfunction "1_1") (pintype "passive"))
      (node (ref "U12") (pin "5") (pinfunction "IN-_5") (pintype "passive"))
    )
    (net (code "65") (name "3.3V") (class "Default")
      (node (ref "C12") (pin "1") (pinfunction "1_1") (pintype "passive"))
      (node (ref "C17") (pin "1") (pinfunction "1_1") (pintype "passive"))
      (node (ref "C2") (pin "1") (pinfunction "1_1") (pintype "passive"))
      (node (ref "C21") (pin "2") (pinfunction "2_2") (pintype "passive"))
      (node (ref "C22") (pin "2") (pinfunction "2_2") (pintype "passive"))
      (node (ref "C23") (pin "2") (pinfunction "2_2") (pintype "passive"))
      (node (ref "C24") (pin "1") (pinfunction "1_1") (pintype "passive"))
      (node (ref "C26") (pin "2") (pinfunction "2_2") (pintype "passive"))
      (node (ref "C7") (pin "1") (pinfunction "1_1") (pintype "passive"))
      (node (ref "R18") (pin "1") (pinfunction "1_1") (pintype "passive"))
      (node (ref "R19") (pin "1") (pinfunction "1_1") (pintype "passive"))
      (node (ref "R31") (pin "1") (pinfunction "1_1") (pintype "passive"))
      (node (ref "R32") (pin "1") (pinfunction "1_1") (pintype "passive"))
      (node (ref "R44") (pin "1") (pinfunction "1_1") (pintype "passive"))
      (node (ref "R45") (pin "1") (pinfunction "1_1") (pintype "passive"))
      (node (ref "R5") (pin "1") (pinfunction "1_1") (pintype "passive"))
      (node (ref "R53") (pin "1") (pinfunction "1_1") (pintype "passive"))
      (node (ref "R6") (pin "1") (pinfunction "1_1") (pintype "passive"))
      (node (ref "U12") (pin "3") (pinfunction "VDD_3") (pintype "passive"))
      (node (ref "U15") (pin "16") (pinfunction "VDD_16") (pintype "passive"))
      (node (ref "U16") (pin "16") (pinfunction "VDD_16") (pintype "passive"))
      (node (ref "U17") (pin "16") (pinfunction "VDD_16") (pintype "passive"))
      (node (ref "U18") (pin "3") (pinfunction "VOUT_3") (pintype "passive"))
      (node (ref "U20") (pin "16") (pinfunction "VDD_16") (pintype "passive"))
      (node (ref "U3") (pin "3") (pinfunction "VDD_3") (pintype "passive"))
      (node (ref "U6") (pin "3") (pinfunction "VDD_3") (pintype "passive"))
      (node (ref "U9") (pin "3") (pinfunction "VDD_3") (pintype "passive"))
    )
    (net (code "66") (name "GND") (class "Default")
      (node (ref "C1") (pin "2") (pinfunction "2_2") (pintype "passive"))
      (node (ref "C11") (pin "2") (pinfunction "2_2") (pintype "passive"))
      (node (ref "C12") (pin "2") (pinfunction "2_2") (pintype "passive"))
      (node (ref "C13") (pin "2") (pinfunction "2_2") (pintype "passive"))
      (node (ref "C14") (pin "2") (pinfunction "2_2") (pintype "passive"))
      (node (ref "C16") (pin "2") (pinfunction "2_2") (pintype "passive"))
      (node (ref "C17") (pin "2") (pinfunction "2_2") (pintype "passive"))
      (node (ref "C18") (pin "2") (pinfunction "2_2") (pintype "passive"))
      (node (ref "C19") (pin "2") (pinfunction "2_2") (pintype "passive"))
      (node (ref "C2") (pin "2") (pinfunction "2_2") (pintype "passive"))
      (node (ref "C21") (pin "1") (pinfunction "1_1") (pintype "passive"))
      (node (ref "C22") (pin "1") (pinfunction "1_1") (pintype "passive"))
      (node (ref "C23") (pin "1") (pinfunction "1_1") (pintype "passive"))
      (node (ref "C24") (pin "2") (pinfunction "2_2") (pintype "passive"))
      (node (ref "C25") (pin "2") (pinfunction "2_2") (pintype "passive"))
      (node (ref "C26") (pin "1") (pinfunction "1_1") (pintype "passive"))
      (node (ref "C3") (pin "2") (pinfunction "2_2") (pintype "passive"))
      (node (ref "C4") (pin "2") (pinfunction "2_2") (pintype "passive"))
      (node (ref "C6") (pin "2") (pinfunction "2_2") (pintype "passive"))
      (node (ref "C7") (pin "2") (pinfunction "2_2") (pintype "passive"))
      (node (ref "C8") (pin "2") (pinfunction "2_2") (pintype "passive"))
      (node (ref "C9") (pin "2") (pinfunction "2_2") (pintype "passive"))
      (node (ref "LD0") (pin "2") (pinfunction "K_2") (pintype "passive"))
      (node (ref "LD1") (pin "2") (pinfunction "K_2") (pintype "passive"))
      (node (ref "LD2") (pin "2") (pinfunction "K_2") (pintype "passive"))
      (node (ref "LD3") (pin "2") (pinfunction "K_2") (pintype "passive"))
      (node (ref "LD4") (pin "2") (pinfunction "K_2") (pintype "passive"))
      (node (ref "LD5") (pin "2") (pinfunction "K_2") (pintype "passive"))
      (node (ref "LD6") (pin "2") (pinfunction "K_2") (pintype "passive"))
      (node (ref "LD7") (pin "2") (pinfunction "K_2") (pintype "passive"))
      (node (ref "LD8") (pin "2") (pinfunction "K_2") (pintype "passive"))
      (node (ref "P1") (pin "1") (pinfunction "1_1") (pintype "passive"))
      (node (ref "P2") (pin "1") (pinfunction "1_1") (pintype "passive"))
      (node (ref "P3") (pin "1") (pinfunction "1_1") (pintype "passive"))
      (node (ref "P4") (pin "1") (pinfunction "1_1") (pintype "passive"))
      (node (ref "P5") (pin "2") (pinfunction "2_2") (pintype "passive"))
      (node (ref "R10") (pin "2") (pinfunction "2_2") (pintype "passive"))
      (node (ref "R11") (pin "2") (pinfunction "2_2") (pintype "passive"))
      (node (ref "R23") (pin "2") (pinfunction "2_2") (pintype "passive"))
      (node (ref "R24") (pin "2") (pinfunction "2_2") (pintype "passive"))
      (node (ref "R36") (pin "2") (pinfunction "2_2") (pintype "passive"))
      (node (ref "R37") (pin "2") (pinfunction "2_2") (pintype "passive"))
      (node (ref "R49") (pin "2") (pinfunction "2_2") (pintype "passive"))
      (node (ref "R50") (pin "2") (pinfunction "2_2") (pintype "passive"))
      (node (ref "R54") (pin "2") (pinfunction "2_2") (pintype "passive"))
      (node (ref "R55") (pin "2") (pinfunction "2_2") (pintype "passive"))
      (node (ref "U1") (pin "2") (pinfunction "GND_2") (pintype "passive"))
      (node (ref "U10") (pin "2") (pinfunction "GND_2") (pintype "passive"))
      (node (ref "U11") (pin "3") (pinfunction "GND_3") (pintype "passive"))
      (node (ref "U12") (pin "1") (pinfunction "REF_1") (pintype "passive"))
      (node (ref "U12") (pin "2") (pinfunction "GND_2") (pintype "passive"))
      (node (ref "U15") (pin "6") (pinfunction "INH_6") (pintype "passive"))
      (node (ref "U15") (pin "7") (pinfunction "VEE_7") (pintype "passive"))
      (node (ref "U15") (pin "8") (pinfunction "VSS_8") (pintype "passive"))
      (node (ref "U16") (pin "6") (pinfunction "INH_6") (pintype "passive"))
      (node (ref "U16") (pin "7") (pinfunction "VEE_7") (pintype "passive"))
      (node (ref "U16") (pin "8") (pinfunction "VSS_8") (pintype "passive"))
      (node (ref "U17") (pin "6") (pinfunction "INH_6") (pintype "passive"))
      (node (ref "U17") (pin "7") (pinfunction "VEE_7") (pintype "passive"))
      (node (ref "U17") (pin "8") (pinfunction "VSS_8") (pintype "passive"))
      (node (ref "U18") (pin "1") (pinfunction "GND_1") (pintype "passive"))
      (node (ref "U2") (pin "3") (pinfunction "GND_3") (pintype "passive"))
      (node (ref "U20") (pin "6") (pinfunction "INH_6") (pintype "passive"))
      (node (ref "U20") (pin "7") (pinfunction "VEE_7") (pintype "passive"))
      (node (ref "U20") (pin "8") (pinfunction "VSS_8") (pintype "passive"))
      (node (ref "U3") (pin "1") (pinfunction "REF_1") (pintype "passive"))
      (node (ref "U3") (pin "2") (pinfunction "GND_2") (pintype "passive"))
      (node (ref "U4") (pin "2") (pinfunction "GND_2") (pintype "passive"))
      (node (ref "U5") (pin "3") (pinfunction "GND_3") (pintype "passive"))
      (node (ref "U6") (pin "1") (pinfunction "REF_1") (pintype "passive"))
      (node (ref "U6") (pin "2") (pinfunction "GND_2") (pintype "passive"))
      (node (ref "U7") (pin "2") (pinfunction "GND_2") (pintype "passive"))
      (node (ref "U8") (pin "3") (pinfunction "GND_3") (pintype "passive"))
      (node (ref "U9") (pin "1") (pinfunction "REF_1") (pintype "passive"))
      (node (ref "U9") (pin "2") (pinfunction "GND_2") (pintype "passive"))
      (node (ref "Z1") (pin "A") (pinfunction "A_A") (pintype "passive"))
    )
    (net (code "67") (name "Net-(LD0-A)") (class "Default")
      (node (ref "LD0") (pin "1") (pinfunction "A_1") (pintype "passive"))
      (node (ref "R53") (pin "2") (pinfunction "2_2") (pintype "passive"))
    )
    (net (code "68") (name "Net-(LD1-A)") (class "Default")
      (node (ref "LD1") (pin "1") (pinfunction "A_1") (pintype "passive"))
      (node (ref "R7") (pin "2") (pinfunction "2_2") (pintype "passive"))
    )
    (net (code "69") (name "Net-(LD2-A)") (class "Default")
      (node (ref "LD2") (pin "1") (pinfunction "A_1") (pintype "passive"))
      (node (ref "R8") (pin "2") (pinfunction "2_2") (pintype "passive"))
    )
    (net (code "70") (name "Net-(LD3-A)") (class "Default")
      (node (ref "LD3") (pin "1") (pinfunction "A_1") (pintype "passive"))
      (node (ref "R20") (pin "2") (pinfunction "2_2") (pintype "passive"))
    )
    (net (code "71") (name "Net-(LD4-A)") (class "Default")
      (node (ref "LD4") (pin "1") (pinfunction "A_1") (pintype "passive"))
      (node (ref "R21") (pin "2") (pinfunction "2_2") (pintype "passive"))
    )
    (net (code "72") (name "Net-(LD5-A)") (class "Default")
      (node (ref "LD5") (pin "1") (pinfunction "A_1") (pintype "passive"))
      (node (ref "R33") (pin "2") (pinfunction "2_2") (pintype "passive"))
    )
    (net (code "73") (name "Net-(LD6-A)") (class "Default")
      (node (ref "LD6") (pin "1") (pinfunction "A_1") (pintype "passive"))
      (node (ref "R34") (pin "2") (pinfunction "2_2") (pintype "passive"))
    )
    (net (code "74") (name "Net-(LD7-A)") (class "Default")
      (node (ref "LD7") (pin "1") (pinfunction "A_1") (pintype "passive"))
      (node (ref "R46") (pin "2") (pinfunction "2_2") (pintype "passive"))
    )
    (net (code "75") (name "Net-(LD8-A)") (class "Default")
      (node (ref "LD8") (pin "1") (pinfunction "A_1") (pintype "passive"))
      (node (ref "R47") (pin "2") (pinfunction "2_2") (pintype "passive"))
    )
    (net (code "76") (name "Net-(P1-Pad4)") (class "Default")
      (node (ref "P1") (pin "4") (pinfunction "4_4") (pintype "passive"))
      (node (ref "R1") (pin "1") (pinfunction "1_1") (pintype "passive"))
    )
    (net (code "77") (name "Net-(P1-Pad5)") (class "Default")
      (node (ref "P1") (pin "5") (pinfunction "5_5") (pintype "passive"))
      (node (ref "R2") (pin "1") (pinfunction "1_1") (pintype "passive"))
    )
    (net (code "78") (name "Net-(P1-Pad6)") (class "Default")
      (node (ref "P1") (pin "6") (pinfunction "6_6") (pintype "passive"))
      (node (ref "R3") (pin "1") (pinfunction "1_1") (pintype "passive"))
    )
    (net (code "79") (name "Net-(P1-Pad7)") (class "Default")
      (node (ref "P1") (pin "7") (pinfunction "7_7") (pintype "passive"))
      (node (ref "R4") (pin "1") (pinfunction "1_1") (pintype "passive"))
    )
    (net (code "80") (name "Net-(P1-Pad10)") (class "Default")
      (node (ref "P1") (pin "10") (pinfunction "10_10") (pintype "passive"))
      (node (ref "R60") (pin "1") (pinfunction "1_1") (pintype "passive"))
    )
    (net (code "81") (name "Net-(P2-Pad4)") (class "Default")
      (node (ref "P2") (pin "4") (pinfunction "4_4") (pintype "passive"))
      (node (ref "R14") (pin "1") (pinfunction "1_1") (pintype "passive"))
    )
    (net (code "82") (name "Net-(P2-Pad5)") (class "Default")
      (node (ref "P2") (pin "5") (pinfunction "5_5") (pintype "passive"))
      (node (ref "R15") (pin "1") (pinfunction "1_1") (pintype "passive"))
    )
    (net (code "83") (name "Net-(P2-Pad6)") (class "Default")
      (node (ref "P2") (pin "6") (pinfunction "6_6") (pintype "passive"))
      (node (ref "R16") (pin "1") (pinfunction "1_1") (pintype "passive"))
    )
    (net (code "84") (name "Net-(P2-Pad7)") (class "Default")
      (node (ref "P2") (pin "7") (pinfunction "7_7") (pintype "passive"))
      (node (ref "R17") (pin "1") (pinfunction "1_1") (pintype "passive"))
    )
    (net (code "85") (name "Net-(P2-Pad10)") (class "Default")
      (node (ref "P2") (pin "10") (pinfunction "10_10") (pintype "passive"))
      (node (ref "R61") (pin "1") (pinfunction "1_1") (pintype "passive"))
    )
    (net (code "86") (name "Net-(P3-Pad4)") (class "Default")
      (node (ref "P3") (pin "4") (pinfunction "4_4") (pintype "passive"))
      (node (ref "R27") (pin "1") (pinfunction "1_1") (pintype "passive"))
    )
    (net (code "87") (name "Net-(P3-Pad5)") (class "Default")
      (node (ref "P3") (pin "5") (pinfunction "5_5") (pintype "passive"))
      (node (ref "R28") (pin "1") (pinfunction "1_1") (pintype "passive"))
    )
    (net (code "88") (name "Net-(P3-Pad6)") (class "Default")
      (node (ref "P3") (pin "6") (pinfunction "6_6") (pintype "passive"))
      (node (ref "R29") (pin "1") (pinfunction "1_1") (pintype "passive"))
    )
    (net (code "89") (name "Net-(P3-Pad7)") (class "Default")
      (node (ref "P3") (pin "7") (pinfunction "7_7") (pintype "passive"))
      (node (ref "R30") (pin "1") (pinfunction "1_1") (pintype "passive"))
    )
    (net (code "90") (name "Net-(P3-Pad10)") (class "Default")
      (node (ref "P3") (pin "10") (pinfunction "10_10") (pintype "passive"))
      (node (ref "R62") (pin "1") (pinfunction "1_1") (pintype "passive"))
    )
    (net (code "91") (name "Net-(P4-Pad4)") (class "Default")
      (node (ref "P4") (pin "4") (pinfunction "4_4") (pintype "passive"))
      (node (ref "R40") (pin "1") (pinfunction "1_1") (pintype "passive"))
    )
    (net (code "92") (name "Net-(P4-Pad5)") (class "Default")
      (node (ref "P4") (pin "5") (pinfunction "5_5") (pintype "passive"))
      (node (ref "R41") (pin "1") (pinfunction "1_1") (pintype "passive"))
    )
    (net (code "93") (name "Net-(P4-Pad6)") (class "Default")
      (node (ref "P4") (pin "6") (pinfunction "6_6") (pintype "passive"))
      (node (ref "R42") (pin "1") (pinfunction "1_1") (pintype "passive"))
    )
    (net (code "94") (name "Net-(P4-Pad7)") (class "Default")
      (node (ref "P4") (pin "7") (pinfunction "7_7") (pintype "passive"))
      (node (ref "R43") (pin "1") (pinfunction "1_1") (pintype "passive"))
    )
    (net (code "95") (name "Net-(P4-Pad10)") (class "Default")
      (node (ref "P4") (pin "10") (pinfunction "10_10") (pintype "passive"))
      (node (ref "R63") (pin "1") (pinfunction "1_1") (pintype "passive"))
    )
    (net (code "96") (name "Net-(U2-SS)") (class "Default")
      (node (ref "C3") (pin "1") (pinfunction "1_1") (pintype "passive"))
      (node (ref "U2") (pin "4") (pinfunction "SS_4") (pintype "passive"))
    )
    (net (code "97") (name "Net-(U3-OUT)") (class "Default")
      (node (ref "R13") (pin "1") (pinfunction "1_1") (pintype "passive"))
      (node (ref "U3") (pin "6") (pinfunction "OUT_6") (pintype "passive"))
    )
    (net (code "98") (name "Net-(U5-SS)") (class "Default")
      (node (ref "C8") (pin "1") (pinfunction "1_1") (pintype "passive"))
      (node (ref "U5") (pin "4") (pinfunction "SS_4") (pintype "passive"))
    )
    (net (code "99") (name "Net-(U6-OUT)") (class "Default")
      (node (ref "R26") (pin "1") (pinfunction "1_1") (pintype "passive"))
      (node (ref "U6") (pin "6") (pinfunction "OUT_6") (pintype "passive"))
    )
    (net (code "100") (name "Net-(U8-SS)") (class "Default")
      (node (ref "C13") (pin "1") (pinfunction "1_1") (pintype "passive"))
      (node (ref "U8") (pin "4") (pinfunction "SS_4") (pintype "passive"))
    )
    (net (code "101") (name "Net-(U9-OUT)") (class "Default")
      (node (ref "R39") (pin "1") (pinfunction "1_1") (pintype "passive"))
      (node (ref "U9") (pin "6") (pinfunction "OUT_6") (pintype "passive"))
    )
    (net (code "102") (name "Net-(U11-SS)") (class "Default")
      (node (ref "C18") (pin "1") (pinfunction "1_1") (pintype "passive"))
      (node (ref "U11") (pin "4") (pinfunction "SS_4") (pintype "passive"))
    )
    (net (code "103") (name "Net-(U12-OUT)") (class "Default")
      (node (ref "R52") (pin "1") (pinfunction "1_1") (pintype "passive"))
      (node (ref "U12") (pin "6") (pinfunction "OUT_6") (pintype "passive"))
    )
    (net (code "104") (name "unconnected-(P1-Pad3)") (class "Default")
      (node (ref "P1") (pin "3") (pinfunction "3_3") (pintype "passive"))
    )
    (net (code "105") (name "unconnected-(P2-Pad3)") (class "Default")
      (node (ref "P2") (pin "3") (pinfunction "3_3") (pintype "passive"))
    )
    (net (code "106") (name "unconnected-(P3-Pad3)") (class "Default")
      (node (ref "P3") (pin "3") (pinfunction "3_3") (pintype "passive"))
    )
    (net (code "107") (name "unconnected-(P4-Pad3)") (class "Default")
      (node (ref "P4") (pin "3") (pinfunction "3_3") (pintype "passive"))
    )
  )
)
